# main.net
KiCad netlist of a schematic drawn in Altium Designer
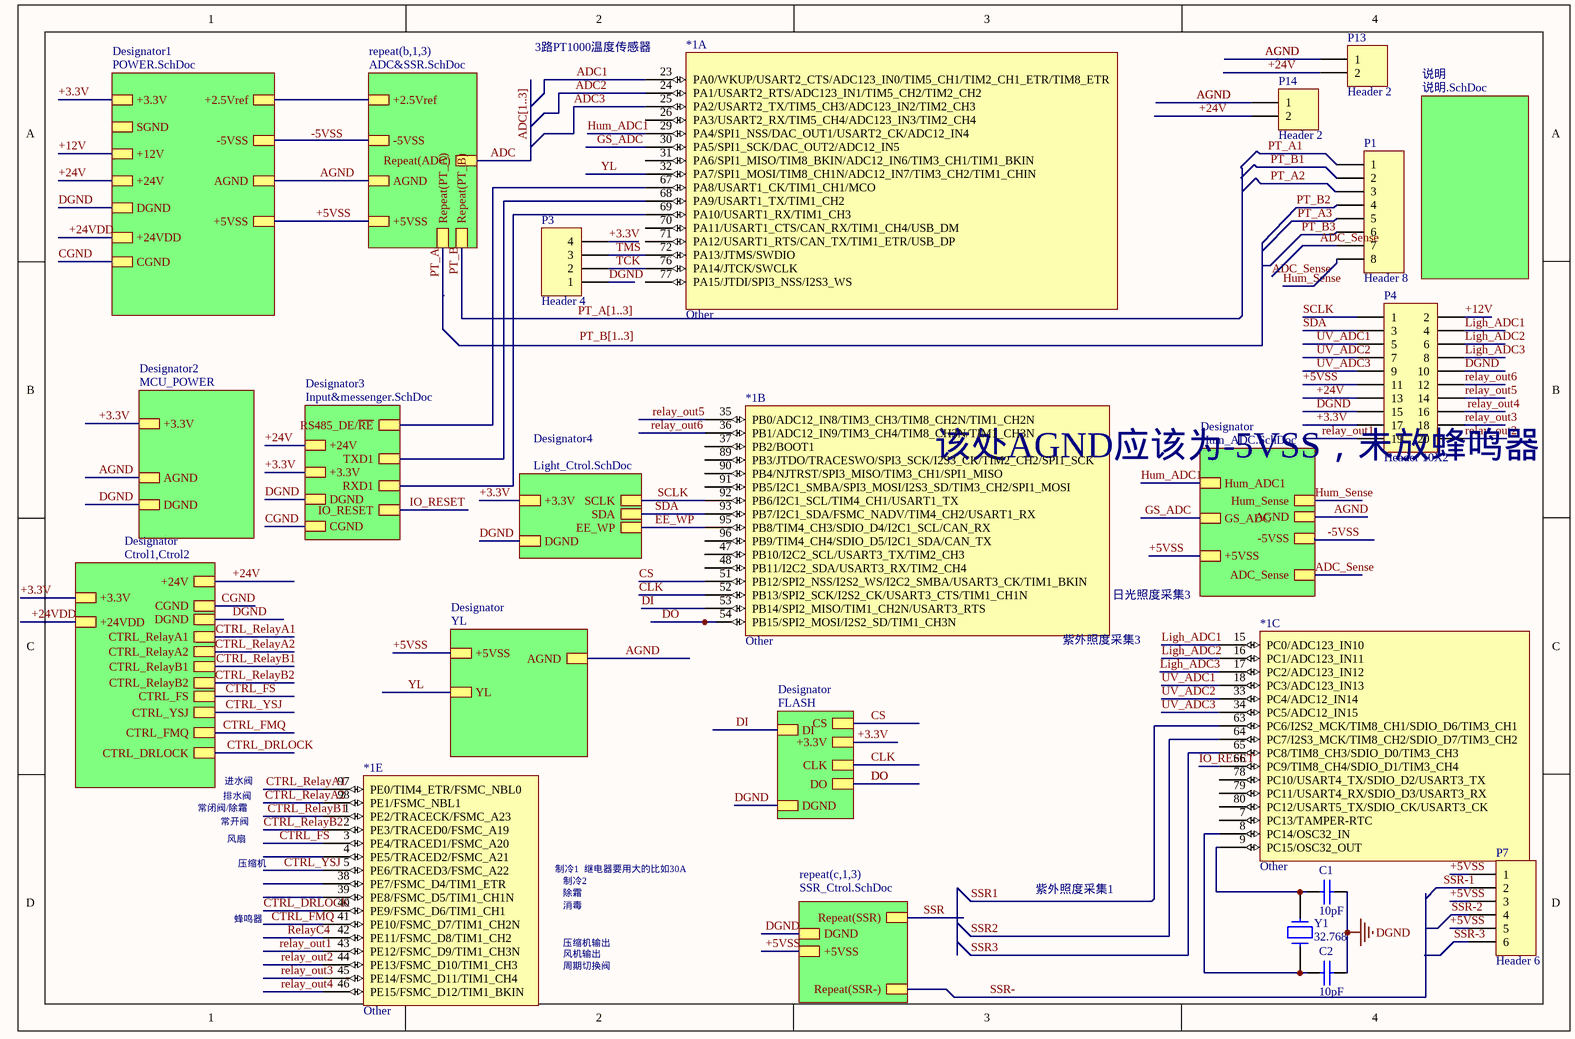
[diagram p0: main.SchDoc]

(export (version "E")
  (design (tool "Eeschema 10.0.6"))
  (components
    (comp (ref "*1")
      (value "Other")
      (footprint "STM-LQFP100_N")
      (libsource (lib "原理图") (part "stm32f103vct6"))
    )
    (comp (ref "C1")
      (value "10pF")
      (footprint "0805C")
      (description "品牌： SAMSUNG(三星)  型号： CL21C100JCANNNC 容值：10pF 精度：±5% 额定电压：100V 材质(温度系数)：C0G C0G")
      (libsource (lib "SCHPCBLIB ") (part "CAP_3"))
    )
    (comp (ref "C2")
      (value "10pF")
      (footprint "0805C")
      (description "品牌： SAMSUNG(三星)  型号： CL21C100JCANNNC 容值：10pF 精度：±5% 额定电压：100V 材质(温度系数)：C0G C0G")
      (libsource (lib "SCHPCBLIB ") (part "CAP_3"))
    )
    (comp (ref "P1")
      (value "Header 8")
      (footprint "CONN-TH-KF7.62-8p")
      (description "DG141V-2.54-8")
      (fields (field (name "PUBLISHER") "Altium Limited"))
      (libsource (lib "Miscellaneous Connectors") (part "Header 8"))
    )
    (comp (ref "P3")
      (value "Header 4")
      (footprint "HDR1X4")
      (fields (field (name "PUBLISHER") "Altium Limited"))
      (libsource (lib "Miscellaneous Connectors") (part "Header 4"))
    )
    (comp (ref "P4")
      (value "Header 10X2")
      (footprint "HDR-TH_20P-P2.54_DC3-2.54-20PAS")
      (fields (field (name "PUBLISHER") "Altium Limited"))
      (libsource (lib "Miscellaneous Connectors") (part "Header 10X2"))
    )
    (comp (ref "P7")
      (value "Header 6")
      (footprint "CONN-TH_6P-P7.62_WJ25C-B-7.62-6P")
      (fields (field (name "PUBLISHER") "Altium Limited"))
      (libsource (lib "Miscellaneous Connectors") (part "Header 6"))
    )
    (comp (ref "P13")
      (value "Header 2")
      (footprint "2P")
      (description "DG141V-2.54-2P")
      (fields (field (name "PUBLISHER") "Altium Limited"))
      (libsource (lib "Miscellaneous Connectors") (part "Header 2"))
    )
    (comp (ref "P14")
      (value "Header 2")
      (footprint "2PPPPP")
      (description "DG141V-2.54-2P")
      (fields (field (name "PUBLISHER") "Altium Limited"))
      (libsource (lib "Miscellaneous Connectors") (part "Header 2"))
    )
    (comp (ref "Y1") (value "32.768") (footprint "XTAL6") (libsource (lib "SCHPCBLIB ") (part "XTAL-2")))
  )
  (nets
    (net (code "2") (name "/+3.3V") (class "Default")
      (node (ref "P3") (pin "4") (pinfunction "4_4") (pintype "passive"))
      (node (ref "P4") (pin "17") (pinfunction "17_17") (pintype "passive"))
    )
    (net (code "3") (name "/+5VSS") (class "Default")
      (node (ref "P4") (pin "11") (pinfunction "11_11") (pintype "passive"))
      (node (ref "P7") (pin "1") (pinfunction "1_1") (pintype "passive"))
      (node (ref "P7") (pin "3") (pinfunction "3_3") (pintype "passive"))
      (node (ref "P7") (pin "5") (pinfunction "5_5") (pintype "passive"))
    )
    (net (code "4") (name "/+12V") (class "Default")
      (node (ref "P4") (pin "2") (pinfunction "2_2") (pintype "passive"))
    )
    (net (code "5") (name "/+24V") (class "Default")
      (node (ref "P13") (pin "2") (pinfunction "2_2") (pintype "passive"))
      (node (ref "P14") (pin "2") (pinfunction "2_2") (pintype "passive"))
      (node (ref "P4") (pin "13") (pinfunction "13_13") (pintype "passive"))
    )
    (net (code "10") (name "/ADC1") (class "Default")
      (node (ref "*1") (pin "23") (pinfunction "PA0/WKUP/USART2_CTS/ADC123_IN0/TIM5_CH1/TIM2_CH1_ETR/TIM8_ETR_23") (pintype "bidirectional"))
    )
    (net (code "11") (name "/ADC2") (class "Default")
      (node (ref "*1") (pin "24") (pinfunction "PA1/USART2_RTS/ADC123_IN1/TIM5_CH2/TIM2_CH2_24") (pintype "bidirectional"))
    )
    (net (code "12") (name "/ADC3") (class "Default")
      (node (ref "*1") (pin "25") (pinfunction "PA2/USART2_TX/TIM5_CH3/ADC123_IN2/TIM2_CH3_25") (pintype "bidirectional"))
    )
    (net (code "14") (name "/ADC_Sense") (class "Default")
      (node (ref "P1") (pin "7") (pinfunction "7_7") (pintype "passive"))
    )
    (net (code "15") (name "/AGND") (class "Default")
      (node (ref "P13") (pin "1") (pinfunction "1_1") (pintype "passive"))
      (node (ref "P14") (pin "1") (pinfunction "1_1") (pintype "passive"))
    )
    (net (code "17") (name "/CLK") (class "Default")
      (node (ref "*1") (pin "52") (pinfunction "PB13/SPI2_SCK/I2S2_CK/USART3_CTS/TIM1_CH1N_52") (pintype "bidirectional"))
    )
    (net (code "18") (name "/CS") (class "Default")
      (node (ref "*1") (pin "51") (pinfunction "PB12/SPI2_NSS/I2S2_WS/I2C2_SMBA/USART3_CK/TIM1_BKIN_51") (pintype "bidirectional"))
    )
    (net (code "19") (name "/CTRL_DRLOCK") (class "Default")
      (node (ref "*1") (pin "40") (pinfunction "PE9/FSMC_D6/TIM1_CH1_40") (pintype "bidirectional"))
    )
    (net (code "20") (name "/CTRL_FMQ") (class "Default")
      (node (ref "*1") (pin "41") (pinfunction "PE10/FSMC_D7/TIM1_CH2N_41") (pintype "bidirectional"))
    )
    (net (code "21") (name "/CTRL_FS") (class "Default")
      (node (ref "*1") (pin "3") (pinfunction "PE4/TRACED1/FSMC_A20_3") (pintype "bidirectional"))
    )
    (net (code "22") (name "/CTRL_RelayA1") (class "Default")
      (node (ref "*1") (pin "97") (pinfunction "PE0/TIM4_ETR/FSMC_NBL0_97") (pintype "bidirectional"))
    )
    (net (code "23") (name "/CTRL_RelayA2") (class "Default")
      (node (ref "*1") (pin "98") (pinfunction "PE1/FSMC_NBL1_98") (pintype "bidirectional"))
    )
    (net (code "24") (name "/CTRL_RelayB1") (class "Default")
      (node (ref "*1") (pin "1") (pinfunction "PE2/TRACECK/FSMC_A23_1") (pintype "bidirectional"))
    )
    (net (code "25") (name "/CTRL_RelayB2") (class "Default")
      (node (ref "*1") (pin "2") (pinfunction "PE3/TRACED0/FSMC_A19_2") (pintype "bidirectional"))
    )
    (net (code "26") (name "/CTRL_YSJ") (class "Default")
      (node (ref "*1") (pin "5") (pinfunction "PE6/TRACED3/FSMC_A22_5") (pintype "bidirectional"))
    )
    (net (code "27") (name "/DI") (class "Default")
      (node (ref "*1") (pin "53") (pinfunction "PB14/SPI2_MISO/TIM1_CH2N/USART3_RTS_53") (pintype "bidirectional"))
    )
    (net (code "28") (name "/DO") (class "Default")
      (node (ref "*1") (pin "54") (pinfunction "PB15/SPI2_MOSI/I2S2_SD/TIM1_CH3N_54") (pintype "bidirectional"))
    )
    (net (code "29") (name "/EE_WP") (class "Default")
      (node (ref "*1") (pin "95") (pinfunction "PB8/TIM4_CH3/SDIO_D4/I2C1_SCL/CAN_RX_95") (pintype "bidirectional"))
    )
    (net (code "30") (name "/GS_ADC") (class "Default")
      (node (ref "*1") (pin "30") (pinfunction "PA5/SPI1_SCK/DAC_OUT2/ADC12_IN5_30") (pintype "bidirectional"))
    )
    (net (code "31") (name "/Hum_ADC1") (class "Default")
      (node (ref "*1") (pin "29") (pinfunction "PA4/SPI1_NSS/DAC_OUT1/USART2_CK/ADC12_IN4_29") (pintype "bidirectional"))
    )
    (net (code "32") (name "/Hum_Sense") (class "Default")
      (node (ref "P1") (pin "8") (pinfunction "8_8") (pintype "passive"))
    )
    (net (code "33") (name "/IO_RESET") (class "Default")
      (node (ref "*1") (pin "66") (pinfunction "PC9/TIM8_CH4/SDIO_D1/TIM3_CH4_66") (pintype "bidirectional"))
    )
    (net (code "34") (name "/Ligh_ADC1") (class "Default")
      (node (ref "*1") (pin "15") (pinfunction "PC0/ADC123_IN10_15") (pintype "bidirectional"))
      (node (ref "P4") (pin "4") (pinfunction "4_4") (pintype "passive"))
    )
    (net (code "35") (name "/Ligh_ADC2") (class "Default")
      (node (ref "*1") (pin "16") (pinfunction "PC1/ADC123_IN11_16") (pintype "bidirectional"))
      (node (ref "P4") (pin "6") (pinfunction "6_6") (pintype "passive"))
    )
    (net (code "36") (name "/Ligh_ADC3") (class "Default")
      (node (ref "*1") (pin "17") (pinfunction "PC2/ADC123_IN12_17") (pintype "bidirectional"))
      (node (ref "P4") (pin "8") (pinfunction "8_8") (pintype "passive"))
    )
    (net (code "38") (name "/PT_A1") (class "Default")
      (node (ref "P1") (pin "1") (pinfunction "1_1") (pintype "passive"))
    )
    (net (code "39") (name "/PT_A2") (class "Default")
      (node (ref "P1") (pin "3") (pinfunction "3_3") (pintype "passive"))
    )
    (net (code "40") (name "/PT_A3") (class "Default")
      (node (ref "P1") (pin "5") (pinfunction "5_5") (pintype "passive"))
    )
    (net (code "43") (name "/PT_B1") (class "Default")
      (node (ref "P1") (pin "2") (pinfunction "2_2") (pintype "passive"))
    )
    (net (code "44") (name "/PT_B2") (class "Default")
      (node (ref "P1") (pin "4") (pinfunction "4_4") (pintype "passive"))
    )
    (net (code "45") (name "/PT_B3") (class "Default")
      (node (ref "P1") (pin "6") (pinfunction "6_6") (pintype "passive"))
    )
    (net (code "47") (name "/RS485_DE{slash}~{RE}") (class "Default")
      (node (ref "*1") (pin "67") (pinfunction "PA8/USART1_CK/TIM1_CH1/MCO_67") (pintype "bidirectional"))
    )
    (net (code "48") (name "/RXD1") (class "Default")
      (node (ref "*1") (pin "69") (pinfunction "PA10/USART1_RX/TIM1_CH3_69") (pintype "bidirectional"))
    )
    (net (code "49") (name "/RelayC4") (class "Default")
      (node (ref "*1") (pin "42") (pinfunction "PE11/FSMC_D8/TIM1_CH2_42") (pintype "bidirectional"))
    )
    (net (code "50") (name "/SCLK") (class "Default")
      (node (ref "*1") (pin "92") (pinfunction "PB6/I2C1_SCL/TIM4_CH1/USART1_TX_92") (pintype "bidirectional"))
      (node (ref "P4") (pin "1") (pinfunction "1_1") (pintype "passive"))
    )
    (net (code "51") (name "/SDA") (class "Default")
      (node (ref "*1") (pin "93") (pinfunction "PB7/I2C1_SDA/FSMC_NADV/TIM4_CH2/USART1_RX_93") (pintype "bidirectional"))
      (node (ref "P4") (pin "3") (pinfunction "3_3") (pintype "passive"))
    )
    (net (code "55") (name "/SSR-1") (class "Default")
      (node (ref "P7") (pin "2") (pinfunction "2_2") (pintype "passive"))
    )
    (net (code "56") (name "/SSR-2") (class "Default")
      (node (ref "P7") (pin "4") (pinfunction "4_4") (pintype "passive"))
    )
    (net (code "57") (name "/SSR-3") (class "Default")
      (node (ref "P7") (pin "6") (pinfunction "6_6") (pintype "passive"))
    )
    (net (code "58") (name "/SSR1") (class "Default")
      (node (ref "*1") (pin "63") (pinfunction "PC6/I2S2_MCK/TIM8_CH1/SDIO_D6/TIM3_CH1_63") (pintype "bidirectional"))
    )
    (net (code "59") (name "/SSR2") (class "Default")
      (node (ref "*1") (pin "64") (pinfunction "PC7/I2S3_MCK/TIM8_CH2/SDIO_D7/TIM3_CH2_64") (pintype "bidirectional"))
    )
    (net (code "60") (name "/SSR3") (class "Default")
      (node (ref "*1") (pin "65") (pinfunction "PC8/TIM8_CH3/SDIO_D0/TIM3_CH3_65") (pintype "bidirectional"))
    )
    (net (code "61") (name "/TCK") (class "Default")
      (node (ref "*1") (pin "76") (pinfunction "PA14/JTCK/SWCLK_76") (pintype "bidirectional"))
      (node (ref "P3") (pin "2") (pinfunction "2_2") (pintype "passive"))
    )
    (net (code "62") (name "/TMS") (class "Default")
      (node (ref "*1") (pin "72") (pinfunction "PA13/JTMS/SWDIO_72") (pintype "bidirectional"))
      (node (ref "P3") (pin "3") (pinfunction "3_3") (pintype "passive"))
    )
    (net (code "63") (name "/TXD1") (class "Default")
      (node (ref "*1") (pin "68") (pinfunction "PA9/USART1_TX/TIM1_CH2_68") (pintype "bidirectional"))
    )
    (net (code "64") (name "/UV_ADC1") (class "Default")
      (node (ref "*1") (pin "18") (pinfunction "PC3/ADC123_IN13_18") (pintype "bidirectional"))
      (node (ref "P4") (pin "5") (pinfunction "5_5") (pintype "passive"))
    )
    (net (code "65") (name "/UV_ADC2") (class "Default")
      (node (ref "*1") (pin "33") (pinfunction "PC4/ADC12_IN14_33") (pintype "bidirectional"))
      (node (ref "P4") (pin "7") (pinfunction "7_7") (pintype "passive"))
    )
    (net (code "66") (name "/UV_ADC3") (class "Default")
      (node (ref "*1") (pin "34") (pinfunction "PC5/ADC12_IN15_34") (pintype "bidirectional"))
      (node (ref "P4") (pin "9") (pinfunction "9_9") (pintype "passive"))
    )
    (net (code "67") (name "/YL") (class "Default")
      (node (ref "*1") (pin "32") (pinfunction "PA7/SPI1_MOSI/TIM8_CH1N/ADC12_IN7/TIM3_CH2/TIM1_CHIN_32") (pintype "bidirectional"))
    )
    (net (code "68") (name "/relay_out1") (class "Default")
      (node (ref "*1") (pin "43") (pinfunction "PE12/FSMC_D9/TIM1_CH3N_43") (pintype "bidirectional"))
      (node (ref "P4") (pin "19") (pinfunction "19_19") (pintype "passive"))
    )
    (net (code "69") (name "/relay_out2") (class "Default")
      (node (ref "*1") (pin "44") (pinfunction "PE13/FSMC_D10/TIM1_CH3_44") (pintype "bidirectional"))
      (node (ref "P4") (pin "20") (pinfunction "20_20") (pintype "passive"))
    )
    (net (code "70") (name "/relay_out3") (class "Default")
      (node (ref "*1") (pin "45") (pinfunction "PE14/FSMC_D11/TIM1_CH4_45") (pintype "bidirectional"))
      (node (ref "P4") (pin "18") (pinfunction "18_18") (pintype "passive"))
    )
    (net (code "71") (name "/relay_out4") (class "Default")
      (node (ref "*1") (pin "46") (pinfunction "PE15/FSMC_D12/TIM1_BKIN_46") (pintype "bidirectional"))
      (node (ref "P4") (pin "16") (pinfunction "16_16") (pintype "passive"))
    )
    (net (code "72") (name "/relay_out5") (class "Default")
      (node (ref "*1") (pin "35") (pinfunction "PB0/ADC12_IN8/TIM3_CH3/TIM8_CH2N/TIM1_CH2N_35") (pintype "bidirectional"))
      (node (ref "P4") (pin "14") (pinfunction "14_14") (pintype "passive"))
    )
    (net (code "73") (name "/relay_out6") (class "Default")
      (node (ref "*1") (pin "36") (pinfunction "PB1/ADC12_IN9/TIM3_CH4/TIM8_CH3N/TIM1_CH3N_36") (pintype "bidirectional"))
      (node (ref "P4") (pin "12") (pinfunction "12_12") (pintype "passive"))
    )
    (net (code "74") (name "DGND") (class "Default")
      (node (ref "C1") (pin "1") (pinfunction "1_1") (pintype "passive"))
      (node (ref "C2") (pin "1") (pinfunction "1_1") (pintype "passive"))
      (node (ref "P3") (pin "1") (pinfunction "1_1") (pintype "passive"))
      (node (ref "P4") (pin "10") (pinfunction "10_10") (pintype "passive"))
      (node (ref "P4") (pin "15") (pinfunction "15_15") (pintype "passive"))
    )
    (net (code "75") (name "Net-(*1C-PC14{slash}OSC32_IN)") (class "Default")
      (node (ref "*1") (pin "8") (pinfunction "PC14/OSC32_IN_8") (pintype "bidirectional"))
      (node (ref "C2") (pin "2") (pinfunction "2_2") (pintype "passive"))
      (node (ref "Y1") (pin "1") (pinfunction "1_1") (pintype "passive"))
    )
    (net (code "76") (name "Net-(*1C-PC15{slash}OSC32_OUT)") (class "Default")
      (node (ref "*1") (pin "9") (pinfunction "PC15/OSC32_OUT_9") (pintype "bidirectional"))
      (node (ref "C1") (pin "2") (pinfunction "2_2") (pintype "passive"))
      (node (ref "Y1") (pin "2") (pinfunction "2_2") (pintype "passive"))
    )
    (net (code "77") (name "unconnected-(*1A-PA3{slash}USART2_RX{slash}TIM5_CH4{slash}ADC123_IN3{slash}TIM2_CH4-Pad26)") (class "Default")
      (node (ref "*1") (pin "26") (pinfunction "PA3/USART2_RX/TIM5_CH4/ADC123_IN3/TIM2_CH4_26") (pintype "bidirectional"))
    )
    (net (code "78") (name "unconnected-(*1A-PA6{slash}SPI1_MISO{slash}TIM8_BKIN{slash}ADC12_IN6{slash}TIM3_CH1{slash}TIM1_BKIN-Pad31)") (class "Default")
      (node (ref "*1") (pin "31") (pinfunction "PA6/SPI1_MISO/TIM8_BKIN/ADC12_IN6/TIM3_CH1/TIM1_BKIN_31") (pintype "bidirectional"))
    )
    (net (code "79") (name "unconnected-(*1A-PA11{slash}USART1_CTS{slash}CAN_RX{slash}TIM1_CH4{slash}USB_DM-Pad70)") (class "Default")
      (node (ref "*1") (pin "70") (pinfunction "PA11/USART1_CTS/CAN_RX/TIM1_CH4/USB_DM_70") (pintype "bidirectional"))
    )
    (net (code "80") (name "unconnected-(*1A-PA12{slash}USART1_RTS{slash}CAN_TX{slash}TIM1_ETR{slash}USB_DP-Pad71)") (class "Default")
      (node (ref "*1") (pin "71") (pinfunction "PA12/USART1_RTS/CAN_TX/TIM1_ETR/USB_DP_71") (pintype "bidirectional"))
    )
    (net (code "81") (name "unconnected-(*1A-PA15{slash}JTDI{slash}SPI3_NSS{slash}I2S3_WS-Pad77)") (class "Default")
      (node (ref "*1") (pin "77") (pinfunction "PA15/JTDI/SPI3_NSS/I2S3_WS_77") (pintype "bidirectional"))
    )
    (net (code "82") (name "unconnected-(*1B-PB2{slash}BOOT1-Pad37)") (class "Default")
      (node (ref "*1") (pin "37") (pinfunction "PB2/BOOT1_37") (pintype "bidirectional"))
    )
    (net (code "83") (name "unconnected-(*1B-PB3{slash}JTDO{slash}TRACESWO{slash}SPI3_SCK{slash}I2S3_CK{slash}TIM2_CH2{slash}SPI1_SCK-Pad89)") (class "Default")
      (node (ref "*1") (pin "89") (pinfunction "PB3/JTDO/TRACESWO/SPI3_SCK/I2S3_CK/TIM2_CH2/SPI1_SCK_89") (pintype "bidirectional"))
    )
    (net (code "84") (name "unconnected-(*1B-PB4{slash}NJTRST{slash}SPI3_MISO{slash}TIM3_CH1{slash}SPI1_MISO-Pad90)") (class "Default")
      (node (ref "*1") (pin "90") (pinfunction "PB4/NJTRST/SPI3_MISO/TIM3_CH1/SPI1_MISO_90") (pintype "bidirectional"))
    )
    (net (code "85") (name "unconnected-(*1B-PB5{slash}I2C1_SMBA{slash}SPI3_MOSI{slash}I2S3_SD{slash}TIM3_CH2{slash}SPI1_MOSI-Pad91)") (class "Default")
      (node (ref "*1") (pin "91") (pinfunction "PB5/I2C1_SMBA/SPI3_MOSI/I2S3_SD/TIM3_CH2/SPI1_MOSI_91") (pintype "bidirectional"))
    )
    (net (code "86") (name "unconnected-(*1B-PB9{slash}TIM4_CH4{slash}SDIO_D5{slash}I2C1_SDA{slash}CAN_TX-Pad96)") (class "Default")
      (node (ref "*1") (pin "96") (pinfunction "PB9/TIM4_CH4/SDIO_D5/I2C1_SDA/CAN_TX_96") (pintype "bidirectional"))
    )
    (net (code "87") (name "unconnected-(*1B-PB10{slash}I2C2_SCL{slash}USART3_TX{slash}TIM2_CH3-Pad47)") (class "Default")
      (node (ref "*1") (pin "47") (pinfunction "PB10/I2C2_SCL/USART3_TX/TIM2_CH3_47") (pintype "bidirectional"))
    )
    (net (code "88") (name "unconnected-(*1B-PB11{slash}I2C2_SDA{slash}USART3_RX{slash}TIM2_CH4-Pad48)") (class "Default")
      (node (ref "*1") (pin "48") (pinfunction "PB11/I2C2_SDA/USART3_RX/TIM2_CH4_48") (pintype "bidirectional"))
    )
    (net (code "89") (name "unconnected-(*1C-PC10{slash}USART4_TX{slash}SDIO_D2{slash}USART3_TX-Pad78)") (class "Default")
      (node (ref "*1") (pin "78") (pinfunction "PC10/USART4_TX/SDIO_D2/USART3_TX_78") (pintype "bidirectional"))
    )
    (net (code "90") (name "unconnected-(*1C-PC11{slash}USART4_RX{slash}SDIO_D3{slash}USART3_RX-Pad79)") (class "Default")
      (node (ref "*1") (pin "79") (pinfunction "PC11/USART4_RX/SDIO_D3/USART3_RX_79") (pintype "bidirectional"))
    )
    (net (code "91") (name "unconnected-(*1C-PC12{slash}USART5_TX{slash}SDIO_CK{slash}USART3_CK-Pad80)") (class "Default")
      (node (ref "*1") (pin "80") (pinfunction "PC12/USART5_TX/SDIO_CK/USART3_CK_80") (pintype "bidirectional"))
    )
    (net (code "92") (name "unconnected-(*1C-PC13{slash}TAMPER-RTC-Pad7)") (class "Default")
      (node (ref "*1") (pin "7") (pinfunction "PC13/TAMPER-RTC_7") (pintype "bidirectional"))
    )
    (net (code "93") (name "unconnected-(*1E-PE5{slash}TRACED2{slash}FSMC_A21-Pad4)") (class "Default")
      (node (ref "*1") (pin "4") (pinfunction "PE5/TRACED2/FSMC_A21_4") (pintype "bidirectional"))
    )
    (net (code "94") (name "unconnected-(*1E-PE7{slash}FSMC_D4{slash}TIM1_ETR-Pad38)") (class "Default")
      (node (ref "*1") (pin "38") (pinfunction "PE7/FSMC_D4/TIM1_ETR_38") (pintype "bidirectional"))
    )
    (net (code "95") (name "unconnected-(*1E-PE8{slash}FSMC_D5{slash}TIM1_CH1N-Pad39)") (class "Default")
      (node (ref "*1") (pin "39") (pinfunction "PE8/FSMC_D5/TIM1_CH1N_39") (pintype "bidirectional"))
    )
  )
)
